# 9_onboard.net
KiCad netlist of a schematic drawn in Altium Designer
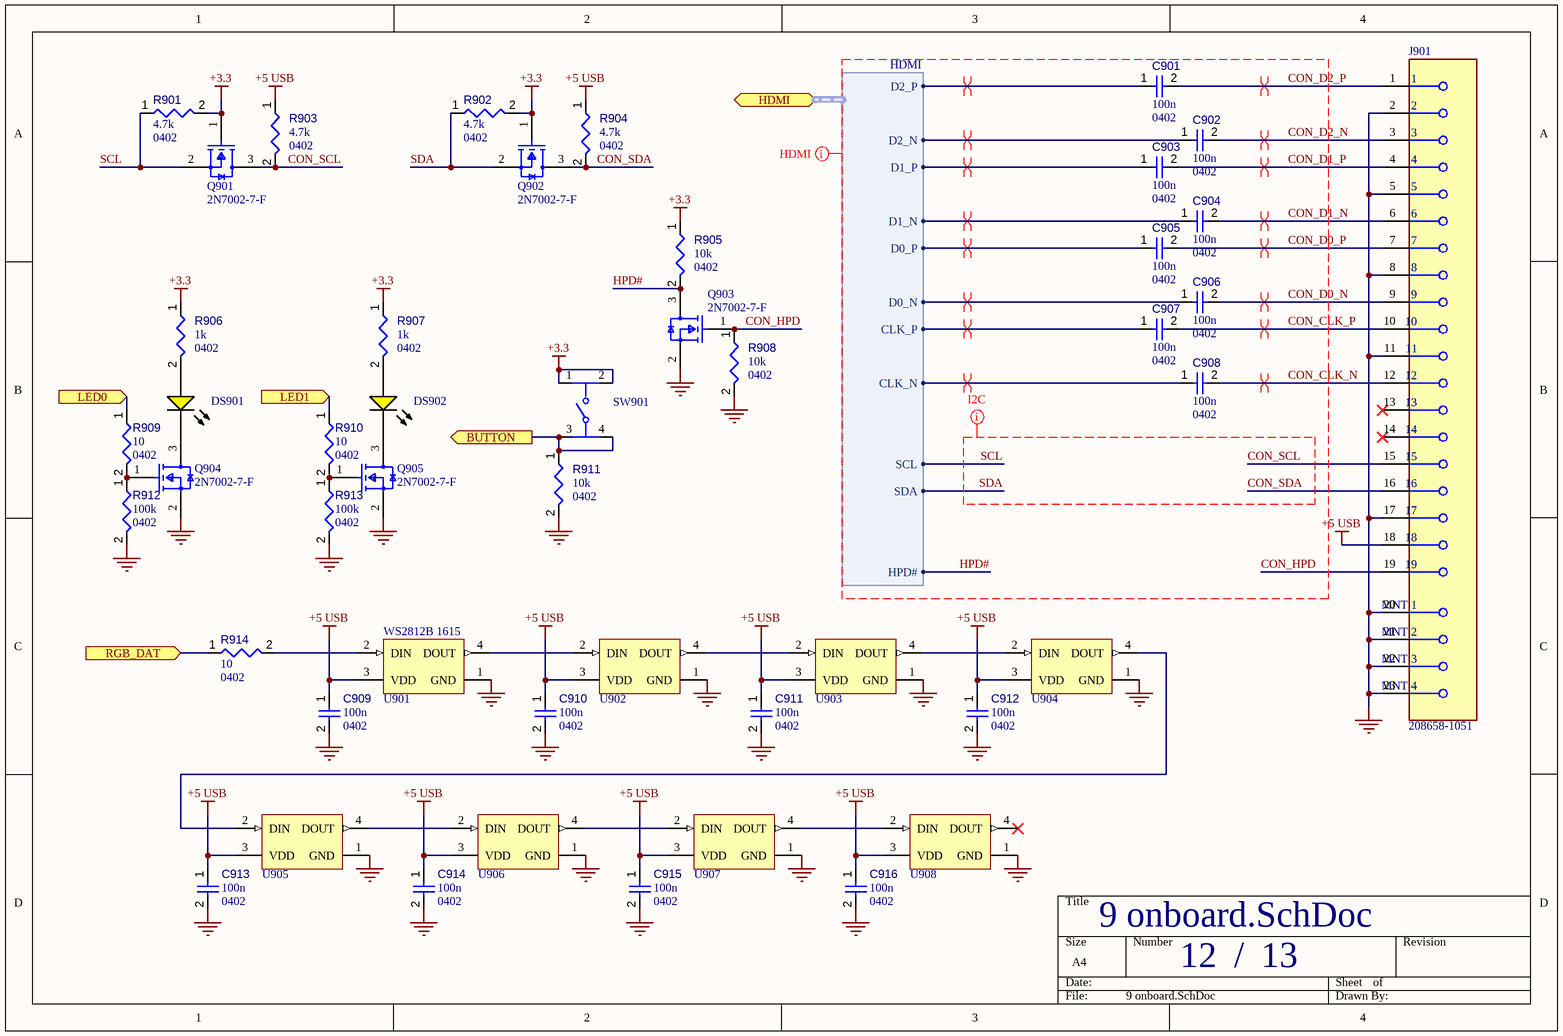
[diagram p0: 9 onboard.SchDoc]

(export (version "E")
  (design (tool "Eeschema 10.0.6"))
  (components
    (comp (ref "C901")
      (value "100n")
      (footprint "CAPC0402(1005)60_L")
      (description "Capacitor")
      (fields (field (name "CASE/PACKAGE") "0402") (field (name "Comment") "Capacitors,0402,100n,16"))
      (libsource (lib "UBC Uncrewed Aircraft Systems") (part "CAP-NP-2"))
    )
    (comp (ref "C902")
      (value "100n")
      (footprint "CAPC0402(1005)60_L")
      (description "Capacitor")
      (fields (field (name "CASE/PACKAGE") "0402") (field (name "Comment") "Capacitors,0402,100n,16"))
      (libsource (lib "UBC Uncrewed Aircraft Systems") (part "CAP-NP-2"))
    )
    (comp (ref "C903")
      (value "100n")
      (footprint "CAPC0402(1005)60_L")
      (description "Capacitor")
      (fields (field (name "CASE/PACKAGE") "0402") (field (name "Comment") "Capacitors,0402,100n,16"))
      (libsource (lib "UBC Uncrewed Aircraft Systems") (part "CAP-NP-2"))
    )
    (comp (ref "C904")
      (value "100n")
      (footprint "CAPC0402(1005)60_L")
      (description "Capacitor")
      (fields (field (name "CASE/PACKAGE") "0402") (field (name "Comment") "Capacitors,0402,100n,16"))
      (libsource (lib "UBC Uncrewed Aircraft Systems") (part "CAP-NP-2"))
    )
    (comp (ref "C905")
      (value "100n")
      (footprint "CAPC0402(1005)60_L")
      (description "Capacitor")
      (fields (field (name "CASE/PACKAGE") "0402") (field (name "Comment") "Capacitors,0402,100n,16"))
      (libsource (lib "UBC Uncrewed Aircraft Systems") (part "CAP-NP-2"))
    )
    (comp (ref "C906")
      (value "100n")
      (footprint "CAPC0402(1005)60_L")
      (description "Capacitor")
      (fields (field (name "CASE/PACKAGE") "0402") (field (name "Comment") "Capacitors,0402,100n,16"))
      (libsource (lib "UBC Uncrewed Aircraft Systems") (part "CAP-NP-2"))
    )
    (comp (ref "C907")
      (value "100n")
      (footprint "CAPC0402(1005)60_L")
      (description "Capacitor")
      (fields (field (name "CASE/PACKAGE") "0402") (field (name "Comment") "Capacitors,0402,100n,16"))
      (libsource (lib "UBC Uncrewed Aircraft Systems") (part "CAP-NP-2"))
    )
    (comp (ref "C908")
      (value "100n")
      (footprint "CAPC0402(1005)60_L")
      (description "Capacitor")
      (fields (field (name "CASE/PACKAGE") "0402") (field (name "Comment") "Capacitors,0402,100n,16"))
      (libsource (lib "UBC Uncrewed Aircraft Systems") (part "CAP-NP-2"))
    )
    (comp (ref "C909")
      (value "100n")
      (footprint "CAPC0402(1005)60_L")
      (description "Capacitor")
      (fields (field (name "CASE/PACKAGE") "0402") (field (name "Comment") "Capacitors,0402,100n,16"))
      (libsource (lib "UBC Uncrewed Aircraft Systems") (part "CAP-NP-2"))
    )
    (comp (ref "C910")
      (value "100n")
      (footprint "CAPC0402(1005)60_L")
      (description "Capacitor")
      (fields (field (name "CASE/PACKAGE") "0402") (field (name "Comment") "Capacitors,0402,100n,16"))
      (libsource (lib "UBC Uncrewed Aircraft Systems") (part "CAP-NP-2"))
    )
    (comp (ref "C911")
      (value "100n")
      (footprint "CAPC0402(1005)60_L")
      (description "Capacitor")
      (fields (field (name "CASE/PACKAGE") "0402") (field (name "Comment") "Capacitors,0402,100n,16"))
      (libsource (lib "UBC Uncrewed Aircraft Systems") (part "CAP-NP-2"))
    )
    (comp (ref "C912")
      (value "100n")
      (footprint "CAPC0402(1005)60_L")
      (description "Capacitor")
      (fields (field (name "CASE/PACKAGE") "0402") (field (name "Comment") "Capacitors,0402,100n,16"))
      (libsource (lib "UBC Uncrewed Aircraft Systems") (part "CAP-NP-2"))
    )
    (comp (ref "C913")
      (value "100n")
      (footprint "CAPC0402(1005)60_L")
      (description "Capacitor")
      (fields (field (name "CASE/PACKAGE") "0402") (field (name "Comment") "Capacitors,0402,100n,16"))
      (libsource (lib "UBC Uncrewed Aircraft Systems") (part "CAP-NP-2"))
    )
    (comp (ref "C914")
      (value "100n")
      (footprint "CAPC0402(1005)60_L")
      (description "Capacitor")
      (fields (field (name "CASE/PACKAGE") "0402") (field (name "Comment") "Capacitors,0402,100n,16"))
      (libsource (lib "UBC Uncrewed Aircraft Systems") (part "CAP-NP-2"))
    )
    (comp (ref "C915")
      (value "100n")
      (footprint "CAPC0402(1005)60_L")
      (description "Capacitor")
      (fields (field (name "CASE/PACKAGE") "0402") (field (name "Comment") "Capacitors,0402,100n,16"))
      (libsource (lib "UBC Uncrewed Aircraft Systems") (part "CAP-NP-2"))
    )
    (comp (ref "C916")
      (value "100n")
      (footprint "CAPC0402(1005)60_L")
      (description "Capacitor")
      (fields (field (name "CASE/PACKAGE") "0402") (field (name "Comment") "Capacitors,0402,100n,16"))
      (libsource (lib "UBC Uncrewed Aircraft Systems") (part "CAP-NP-2"))
    )
    (comp (ref "DS901")
      (value "SML-LX0603YW-TR")
      (footprint "LUMX-SML-LX0603_V")
      (fields (field (name "MANUFACTURER") "Lumex"))
      (libsource (lib "Altium Content Vault") (part "LED-YELLOW-AK-2"))
    )
    (comp (ref "DS902")
      (value "SML-LX0603YW-TR")
      (footprint "LUMX-SML-LX0603_V")
      (fields (field (name "MANUFACTURER") "Lumex"))
      (libsource (lib "Altium Content Vault") (part "LED-YELLOW-AK-2"))
    )
    (comp (ref "J901")
      (value "208658-1051")
      (footprint "FP-208658-1051-MFG")
      (description "CONN RCPT HDMI V2.1 19POS SMD RA")
      (libsource (lib "Altium Content Vault") (part "2f8f9bd2e294963b88b490f2f824c1f"))
    )
    (comp (ref "Q901")
      (value "2N7002-7-F")
      (footprint "FP-SOT23-MFG")
      (description "MOSFET N-CH 60V 115MA SOT23-3")
      (fields (field (name "VOLTAGE") "60V"))
      (libsource (lib "Altium Content Vault") (part "3b9c635fedb024a5347a57b145af9cc"))
    )
    (comp (ref "Q902")
      (value "2N7002-7-F")
      (footprint "FP-SOT23-MFG")
      (description "MOSFET N-CH 60V 115MA SOT23-3")
      (fields (field (name "VOLTAGE") "60V"))
      (libsource (lib "Altium Content Vault") (part "3b9c635fedb024a5347a57b145af9cc"))
    )
    (comp (ref "Q903")
      (value "2N7002-7-F")
      (footprint "FP-SOT23-MFG")
      (description "MOSFET N-CH 60V 115MA SOT23-3")
      (fields (field (name "VOLTAGE") "60V"))
      (libsource (lib "Altium Content Vault") (part "3b9c635fedb024a5347a57b145af9cc"))
    )
    (comp (ref "Q904")
      (value "2N7002-7-F")
      (footprint "FP-SOT23-MFG")
      (description "MOSFET N-CH 60V 115MA SOT23-3")
      (fields (field (name "VOLTAGE") "60V"))
      (libsource (lib "Altium Content Vault") (part "3b9c635fedb024a5347a57b145af9cc"))
    )
    (comp (ref "Q905")
      (value "2N7002-7-F")
      (footprint "FP-SOT23-MFG")
      (description "MOSFET N-CH 60V 115MA SOT23-3")
      (fields (field (name "VOLTAGE") "60V"))
      (libsource (lib "Altium Content Vault") (part "3b9c635fedb024a5347a57b145af9cc"))
    )
    (comp (ref "R901")
      (value "4.7k")
      (footprint "RESC0402(1005)_L")
      (description "Resistor")
      (fields (field (name "CASE/PACKAGE") "0402") (field (name "Comment") "Resistors,0402,4.7k"))
      (libsource (lib "UBC Uncrewed Aircraft Systems") (part "RES-2"))
    )
    (comp (ref "R902")
      (value "4.7k")
      (footprint "RESC0402(1005)_L")
      (description "Resistor")
      (fields (field (name "CASE/PACKAGE") "0402") (field (name "Comment") "Resistors,0402,4.7k"))
      (libsource (lib "UBC Uncrewed Aircraft Systems") (part "RES-2"))
    )
    (comp (ref "R903")
      (value "4.7k")
      (footprint "RESC0402(1005)_L")
      (description "Resistor")
      (fields (field (name "CASE/PACKAGE") "0402") (field (name "Comment") "Resistors,0402,4.7k"))
      (libsource (lib "UBC Uncrewed Aircraft Systems") (part "RES-2"))
    )
    (comp (ref "R904")
      (value "4.7k")
      (footprint "RESC0402(1005)_L")
      (description "Resistor")
      (fields (field (name "CASE/PACKAGE") "0402") (field (name "Comment") "Resistors,0402,4.7k"))
      (libsource (lib "UBC Uncrewed Aircraft Systems") (part "RES-2"))
    )
    (comp (ref "R905")
      (value "10k")
      (footprint "RESC0402(1005)_L")
      (description "Resistor")
      (fields (field (name "CASE/PACKAGE") "0402") (field (name "Comment") "Resistors,0402,10k"))
      (libsource (lib "UBC Uncrewed Aircraft Systems") (part "RES-2"))
    )
    (comp (ref "R906")
      (value "1k")
      (footprint "RESC0402(1005)_L")
      (description "Resistor")
      (fields (field (name "CASE/PACKAGE") "0402") (field (name "Comment") "Resistors,0402,1k"))
      (libsource (lib "UBC Uncrewed Aircraft Systems") (part "RES-2"))
    )
    (comp (ref "R907")
      (value "1k")
      (footprint "RESC0402(1005)_L")
      (description "Resistor")
      (fields (field (name "CASE/PACKAGE") "0402") (field (name "Comment") "Resistors,0402,1k"))
      (libsource (lib "UBC Uncrewed Aircraft Systems") (part "RES-2"))
    )
    (comp (ref "R908")
      (value "10k")
      (footprint "RESC0402(1005)_L")
      (description "Resistor")
      (fields (field (name "CASE/PACKAGE") "0402") (field (name "Comment") "Resistors,0402,10k"))
      (libsource (lib "UBC Uncrewed Aircraft Systems") (part "RES-2"))
    )
    (comp (ref "R909")
      (value "10")
      (footprint "RESC0402(1005)_L")
      (description "Resistor")
      (fields (field (name "CASE/PACKAGE") "0402") (field (name "Comment") "Resistors,0402,10"))
      (libsource (lib "UBC Uncrewed Aircraft Systems") (part "RES-2"))
    )
    (comp (ref "R910")
      (value "10")
      (footprint "RESC0402(1005)_L")
      (description "Resistor")
      (fields (field (name "CASE/PACKAGE") "0402") (field (name "Comment") "Resistors,0402,10"))
      (libsource (lib "UBC Uncrewed Aircraft Systems") (part "RES-2"))
    )
    (comp (ref "R911")
      (value "10k")
      (footprint "RESC0402(1005)_L")
      (description "Resistor")
      (fields (field (name "CASE/PACKAGE") "0402") (field (name "Comment") "Resistors,0402,10k"))
      (libsource (lib "UBC Uncrewed Aircraft Systems") (part "RES-2"))
    )
    (comp (ref "R912")
      (value "100k")
      (footprint "RESC0402(1005)_L")
      (description "Resistor")
      (fields
        (field (name "CASE/PACKAGE") "0402")
        (field (name "TOLERANCE") "1%")
        (field (name "Comment") "Resistors,0402,1%,100k")
      )
      (libsource (lib "UBC Uncrewed Aircraft Systems") (part "RES-2"))
    )
    (comp (ref "R913")
      (value "100k")
      (footprint "RESC0402(1005)_L")
      (description "Resistor")
      (fields
        (field (name "CASE/PACKAGE") "0402")
        (field (name "TOLERANCE") "1%")
        (field (name "Comment") "Resistors,0402,1%,100k")
      )
      (libsource (lib "UBC Uncrewed Aircraft Systems") (part "RES-2"))
    )
    (comp (ref "R914")
      (value "10")
      (footprint "RESC0402(1005)_L")
      (description "Resistor")
      (fields (field (name "CASE/PACKAGE") "0402") (field (name "Comment") "Resistors,0402,10"))
      (libsource (lib "UBC Uncrewed Aircraft Systems") (part "RES-2"))
    )
    (comp (ref "SW901")
      (value "PTS810SJM250SMTRLFS")
      (footprint "FP-PTS810SJM250SMTRLFS-MFG")
      (description "SWITCH TACTILE SPST-NO 0.05A 16V")
      (libsource (lib "Altium Content Vault") (part "1adf0dd01260c80cf25a44bfd6b99ba"))
    )
    (comp (ref "U901")
      (value "WS2812B 1615")
      (footprint "WS2812B 1615")
      (libsource (lib "JLCPCB Library") (part "WS2812B 1615"))
    )
    (comp (ref "U902")
      (value "WS2812B 1615")
      (footprint "WS2812B 1615")
      (libsource (lib "JLCPCB Library") (part "WS2812B 1615"))
    )
    (comp (ref "U903")
      (value "WS2812B 1615")
      (footprint "WS2812B 1615")
      (libsource (lib "JLCPCB Library") (part "WS2812B 1615"))
    )
    (comp (ref "U904")
      (value "WS2812B 1615")
      (footprint "WS2812B 1615")
      (libsource (lib "JLCPCB Library") (part "WS2812B 1615"))
    )
    (comp (ref "U905")
      (value "WS2812B 1615")
      (footprint "WS2812B 1615")
      (libsource (lib "JLCPCB Library") (part "WS2812B 1615"))
    )
    (comp (ref "U906")
      (value "WS2812B 1615")
      (footprint "WS2812B 1615")
      (libsource (lib "JLCPCB Library") (part "WS2812B 1615"))
    )
    (comp (ref "U907")
      (value "WS2812B 1615")
      (footprint "WS2812B 1615")
      (libsource (lib "JLCPCB Library") (part "WS2812B 1615"))
    )
    (comp (ref "U908")
      (value "WS2812B 1615")
      (footprint "WS2812B 1615")
      (libsource (lib "JLCPCB Library") (part "WS2812B 1615"))
    )
  )
  (nets
    (net (code "2") (name "+3.3") (class "Default")
      (node (ref "Q901") (pin "1") (pinfunction "G_1") (pintype "passive"))
      (node (ref "Q902") (pin "1") (pinfunction "G_1") (pintype "passive"))
      (node (ref "R901") (pin "2") (pinfunction "2_2") (pintype "passive"))
      (node (ref "R902") (pin "2") (pinfunction "2_2") (pintype "passive"))
      (node (ref "R905") (pin "1") (pinfunction "1_1") (pintype "passive"))
      (node (ref "R906") (pin "1") (pinfunction "1_1") (pintype "passive"))
      (node (ref "R907") (pin "1") (pinfunction "1_1") (pintype "passive"))
      (node (ref "SW901") (pin "1") (pinfunction "1_1") (pintype "passive"))
      (node (ref "SW901") (pin "2") (pinfunction "2_2") (pintype "passive"))
    )
    (net (code "3") (name "+5 USB") (class "Default")
      (node (ref "C909") (pin "1") (pinfunction "1_1") (pintype "passive"))
      (node (ref "C910") (pin "1") (pinfunction "1_1") (pintype "passive"))
      (node (ref "C911") (pin "1") (pinfunction "1_1") (pintype "passive"))
      (node (ref "C912") (pin "1") (pinfunction "1_1") (pintype "passive"))
      (node (ref "C913") (pin "1") (pinfunction "1_1") (pintype "passive"))
      (node (ref "C914") (pin "1") (pinfunction "1_1") (pintype "passive"))
      (node (ref "C915") (pin "1") (pinfunction "1_1") (pintype "passive"))
      (node (ref "C916") (pin "1") (pinfunction "1_1") (pintype "passive"))
      (node (ref "J901") (pin "18") (pinfunction "18_18") (pintype "passive"))
      (node (ref "R903") (pin "1") (pinfunction "1_1") (pintype "passive"))
      (node (ref "R904") (pin "1") (pinfunction "1_1") (pintype "passive"))
      (node (ref "U901") (pin "3") (pinfunction "VDD_3") (pintype "power_in"))
      (node (ref "U902") (pin "3") (pinfunction "VDD_3") (pintype "power_in"))
      (node (ref "U903") (pin "3") (pinfunction "VDD_3") (pintype "power_in"))
      (node (ref "U904") (pin "3") (pinfunction "VDD_3") (pintype "power_in"))
      (node (ref "U905") (pin "3") (pinfunction "VDD_3") (pintype "power_in"))
      (node (ref "U906") (pin "3") (pinfunction "VDD_3") (pintype "power_in"))
      (node (ref "U907") (pin "3") (pinfunction "VDD_3") (pintype "power_in"))
      (node (ref "U908") (pin "3") (pinfunction "VDD_3") (pintype "power_in"))
    )
    (net (code "4") (name "/BUTTON") (class "Default")
      (node (ref "R911") (pin "1") (pinfunction "1_1") (pintype "passive"))
      (node (ref "SW901") (pin "3") (pinfunction "3_3") (pintype "passive"))
      (node (ref "SW901") (pin "4") (pinfunction "4_4") (pintype "passive"))
    )
    (net (code "5") (name "/CLK_N") (class "Default")
      (node (ref "C908") (pin "1") (pinfunction "1_1") (pintype "passive"))
    )
    (net (code "6") (name "/CLK_P") (class "Default")
      (node (ref "C907") (pin "1") (pinfunction "1_1") (pintype "passive"))
    )
    (net (code "7") (name "/CON_CLK_N") (class "Default")
      (node (ref "C908") (pin "2") (pinfunction "2_2") (pintype "passive"))
      (node (ref "J901") (pin "12") (pinfunction "12_12") (pintype "passive"))
    )
    (net (code "8") (name "/CON_CLK_P") (class "Default")
      (node (ref "C907") (pin "2") (pinfunction "2_2") (pintype "passive"))
      (node (ref "J901") (pin "10") (pinfunction "10_10") (pintype "passive"))
    )
    (net (code "9") (name "/CON_D0_N") (class "Default")
      (node (ref "C906") (pin "2") (pinfunction "2_2") (pintype "passive"))
      (node (ref "J901") (pin "9") (pinfunction "9_9") (pintype "passive"))
    )
    (net (code "10") (name "/CON_D0_P") (class "Default")
      (node (ref "C905") (pin "2") (pinfunction "2_2") (pintype "passive"))
      (node (ref "J901") (pin "7") (pinfunction "7_7") (pintype "passive"))
    )
    (net (code "11") (name "/CON_D1_N") (class "Default")
      (node (ref "C904") (pin "2") (pinfunction "2_2") (pintype "passive"))
      (node (ref "J901") (pin "6") (pinfunction "6_6") (pintype "passive"))
    )
    (net (code "12") (name "/CON_D1_P") (class "Default")
      (node (ref "C903") (pin "2") (pinfunction "2_2") (pintype "passive"))
      (node (ref "J901") (pin "4") (pinfunction "4_4") (pintype "passive"))
    )
    (net (code "13") (name "/CON_D2_N") (class "Default")
      (node (ref "C902") (pin "2") (pinfunction "2_2") (pintype "passive"))
      (node (ref "J901") (pin "3") (pinfunction "3_3") (pintype "passive"))
    )
    (net (code "14") (name "/CON_D2_P") (class "Default")
      (node (ref "C901") (pin "2") (pinfunction "2_2") (pintype "passive"))
      (node (ref "J901") (pin "1") (pinfunction "1_1") (pintype "passive"))
    )
    (net (code "15") (name "/CON_HPD") (class "Default")
      (node (ref "J901") (pin "19") (pinfunction "19_19") (pintype "passive"))
      (node (ref "Q903") (pin "1") (pinfunction "G_1") (pintype "passive"))
      (node (ref "R908") (pin "1") (pinfunction "1_1") (pintype "passive"))
    )
    (net (code "16") (name "/CON_SCL") (class "Default")
      (node (ref "J901") (pin "15") (pinfunction "15_15") (pintype "passive"))
      (node (ref "Q901") (pin "3") (pinfunction "D_3") (pintype "passive"))
      (node (ref "R903") (pin "2") (pinfunction "2_2") (pintype "passive"))
    )
    (net (code "17") (name "/CON_SDA") (class "Default")
      (node (ref "J901") (pin "16") (pinfunction "16_16") (pintype "passive"))
      (node (ref "Q902") (pin "3") (pinfunction "D_3") (pintype "passive"))
      (node (ref "R904") (pin "2") (pinfunction "2_2") (pintype "passive"))
    )
    (net (code "18") (name "/D0_N") (class "Default")
      (node (ref "C906") (pin "1") (pinfunction "1_1") (pintype "passive"))
    )
    (net (code "19") (name "/D0_P") (class "Default")
      (node (ref "C905") (pin "1") (pinfunction "1_1") (pintype "passive"))
    )
    (net (code "20") (name "/D1_N") (class "Default")
      (node (ref "C904") (pin "1") (pinfunction "1_1") (pintype "passive"))
    )
    (net (code "21") (name "/D1_P") (class "Default")
      (node (ref "C903") (pin "1") (pinfunction "1_1") (pintype "passive"))
    )
    (net (code "22") (name "/D2_N") (class "Default")
      (node (ref "C902") (pin "1") (pinfunction "1_1") (pintype "passive"))
    )
    (net (code "23") (name "/D2_P") (class "Default")
      (node (ref "C901") (pin "1") (pinfunction "1_1") (pintype "passive"))
    )
    (net (code "24") (name "/HPD#") (class "Default")
      (node (ref "Q903") (pin "3") (pinfunction "D_3") (pintype "passive"))
      (node (ref "R905") (pin "2") (pinfunction "2_2") (pintype "passive"))
    )
    (net (code "25") (name "/LED0") (class "Default")
      (node (ref "R909") (pin "1") (pinfunction "1_1") (pintype "passive"))
    )
    (net (code "26") (name "/LED1") (class "Default")
      (node (ref "R910") (pin "1") (pinfunction "1_1") (pintype "passive"))
    )
    (net (code "27") (name "/RGB_DAT") (class "Default")
      (node (ref "R914") (pin "1") (pinfunction "1_1") (pintype "passive"))
    )
    (net (code "28") (name "/SCL") (class "Default")
      (node (ref "Q901") (pin "2") (pinfunction "S_2") (pintype "passive"))
      (node (ref "R901") (pin "1") (pinfunction "1_1") (pintype "passive"))
    )
    (net (code "29") (name "/SDA") (class "Default")
      (node (ref "Q902") (pin "2") (pinfunction "S_2") (pintype "passive"))
      (node (ref "R902") (pin "1") (pinfunction "1_1") (pintype "passive"))
    )
    (net (code "31") (name "GND") (class "Default")
      (node (ref "C909") (pin "2") (pinfunction "2_2") (pintype "passive"))
      (node (ref "C910") (pin "2") (pinfunction "2_2") (pintype "passive"))
      (node (ref "C911") (pin "2") (pinfunction "2_2") (pintype "passive"))
      (node (ref "C912") (pin "2") (pinfunction "2_2") (pintype "passive"))
      (node (ref "C913") (pin "2") (pinfunction "2_2") (pintype "passive"))
      (node (ref "C914") (pin "2") (pinfunction "2_2") (pintype "passive"))
      (node (ref "C915") (pin "2") (pinfunction "2_2") (pintype "passive"))
      (node (ref "C916") (pin "2") (pinfunction "2_2") (pintype "passive"))
      (node (ref "J901") (pin "11") (pinfunction "11_11") (pintype "passive"))
      (node (ref "J901") (pin "17") (pinfunction "17_17") (pintype "passive"))
      (node (ref "J901") (pin "2") (pinfunction "2_2") (pintype "passive"))
      (node (ref "J901") (pin "20") (pinfunction "MNT_1_20") (pintype "passive"))
      (node (ref "J901") (pin "21") (pinfunction "MNT_2_21") (pintype "passive"))
      (node (ref "J901") (pin "22") (pinfunction "MNT_3_22") (pintype "passive"))
      (node (ref "J901") (pin "23") (pinfunction "MNT_4_23") (pintype "passive"))
      (node (ref "J901") (pin "5") (pinfunction "5_5") (pintype "passive"))
      (node (ref "J901") (pin "8") (pinfunction "8_8") (pintype "passive"))
      (node (ref "Q903") (pin "2") (pinfunction "S_2") (pintype "passive"))
      (node (ref "Q904") (pin "2") (pinfunction "S_2") (pintype "passive"))
      (node (ref "Q905") (pin "2") (pinfunction "S_2") (pintype "passive"))
      (node (ref "R908") (pin "2") (pinfunction "2_2") (pintype "passive"))
      (node (ref "R911") (pin "2") (pinfunction "2_2") (pintype "passive"))
      (node (ref "R912") (pin "2") (pinfunction "2_2") (pintype "passive"))
      (node (ref "R913") (pin "2") (pinfunction "2_2") (pintype "passive"))
      (node (ref "U901") (pin "1") (pinfunction "GND_1") (pintype "power_in"))
      (node (ref "U902") (pin "1") (pinfunction "GND_1") (pintype "power_in"))
      (node (ref "U903") (pin "1") (pinfunction "GND_1") (pintype "power_in"))
      (node (ref "U904") (pin "1") (pinfunction "GND_1") (pintype "power_in"))
      (node (ref "U905") (pin "1") (pinfunction "GND_1") (pintype "power_in"))
      (node (ref "U906") (pin "1") (pinfunction "GND_1") (pintype "power_in"))
      (node (ref "U907") (pin "1") (pinfunction "GND_1") (pintype "power_in"))
      (node (ref "U908") (pin "1") (pinfunction "GND_1") (pintype "power_in"))
    )
    (net (code "32") (name "Net-(DS901-A)") (class "Default")
      (node (ref "DS901") (pin "1") (pinfunction "A_1") (pintype "passive"))
      (node (ref "R906") (pin "2") (pinfunction "2_2") (pintype "passive"))
    )
    (net (code "33") (name "Net-(DS901-K)") (class "Default")
      (node (ref "DS901") (pin "2") (pinfunction "K_2") (pintype "passive"))
      (node (ref "Q904") (pin "3") (pinfunction "D_3") (pintype "passive"))
    )
    (net (code "34") (name "Net-(DS902-A)") (class "Default")
      (node (ref "DS902") (pin "1") (pinfunction "A_1") (pintype "passive"))
      (node (ref "R907") (pin "2") (pinfunction "2_2") (pintype "passive"))
    )
    (net (code "35") (name "Net-(DS902-K)") (class "Default")
      (node (ref "DS902") (pin "2") (pinfunction "K_2") (pintype "passive"))
      (node (ref "Q905") (pin "3") (pinfunction "D_3") (pintype "passive"))
    )
    (net (code "36") (name "Net-(Q904-G)") (class "Default")
      (node (ref "Q904") (pin "1") (pinfunction "G_1") (pintype "passive"))
      (node (ref "R909") (pin "2") (pinfunction "2_2") (pintype "passive"))
      (node (ref "R912") (pin "1") (pinfunction "1_1") (pintype "passive"))
    )
    (net (code "37") (name "Net-(Q905-G)") (class "Default")
      (node (ref "Q905") (pin "1") (pinfunction "G_1") (pintype "passive"))
      (node (ref "R910") (pin "2") (pinfunction "2_2") (pintype "passive"))
      (node (ref "R913") (pin "1") (pinfunction "1_1") (pintype "passive"))
    )
    (net (code "38") (name "Net-(U901-DIN)") (class "Default")
      (node (ref "R914") (pin "2") (pinfunction "2_2") (pintype "passive"))
      (node (ref "U901") (pin "2") (pinfunction "DIN_2") (pintype "input"))
    )
    (net (code "39") (name "Net-(U901-DOUT)") (class "Default")
      (node (ref "U901") (pin "4") (pinfunction "DOUT_4") (pintype "output"))
      (node (ref "U902") (pin "2") (pinfunction "DIN_2") (pintype "input"))
    )
    (net (code "40") (name "Net-(U902-DOUT)") (class "Default")
      (node (ref "U902") (pin "4") (pinfunction "DOUT_4") (pintype "output"))
      (node (ref "U903") (pin "2") (pinfunction "DIN_2") (pintype "input"))
    )
    (net (code "41") (name "Net-(U903-DOUT)") (class "Default")
      (node (ref "U903") (pin "4") (pinfunction "DOUT_4") (pintype "output"))
      (node (ref "U904") (pin "2") (pinfunction "DIN_2") (pintype "input"))
    )
    (net (code "42") (name "Net-(U904-DOUT)") (class "Default")
      (node (ref "U904") (pin "4") (pinfunction "DOUT_4") (pintype "output"))
      (node (ref "U905") (pin "2") (pinfunction "DIN_2") (pintype "input"))
    )
    (net (code "43") (name "Net-(U905-DOUT)") (class "Default")
      (node (ref "U905") (pin "4") (pinfunction "DOUT_4") (pintype "output"))
      (node (ref "U906") (pin "2") (pinfunction "DIN_2") (pintype "input"))
    )
    (net (code "44") (name "Net-(U906-DOUT)") (class "Default")
      (node (ref "U906") (pin "4") (pinfunction "DOUT_4") (pintype "output"))
      (node (ref "U907") (pin "2") (pinfunction "DIN_2") (pintype "input"))
    )
    (net (code "45") (name "Net-(U907-DOUT)") (class "Default")
      (node (ref "U907") (pin "4") (pinfunction "DOUT_4") (pintype "output"))
      (node (ref "U908") (pin "2") (pinfunction "DIN_2") (pintype "input"))
    )
    (net (code "46") (name "unconnected-(J901-Pad13)") (class "Default")
      (node (ref "J901") (pin "13") (pinfunction "13_13") (pintype "passive+no_connect"))
    )
    (net (code "47") (name "unconnected-(J901-Pad14)") (class "Default")
      (node (ref "J901") (pin "14") (pinfunction "14_14") (pintype "passive+no_connect"))
    )
    (net (code "48") (name "unconnected-(U908-DOUT-Pad4)") (class "Default")
      (node (ref "U908") (pin "4") (pinfunction "DOUT_4") (pintype "output+no_connect"))
    )
  )
)
